# 1x24_relayBoard_011.net
KiCad netlist of a schematic drawn in EAGLE
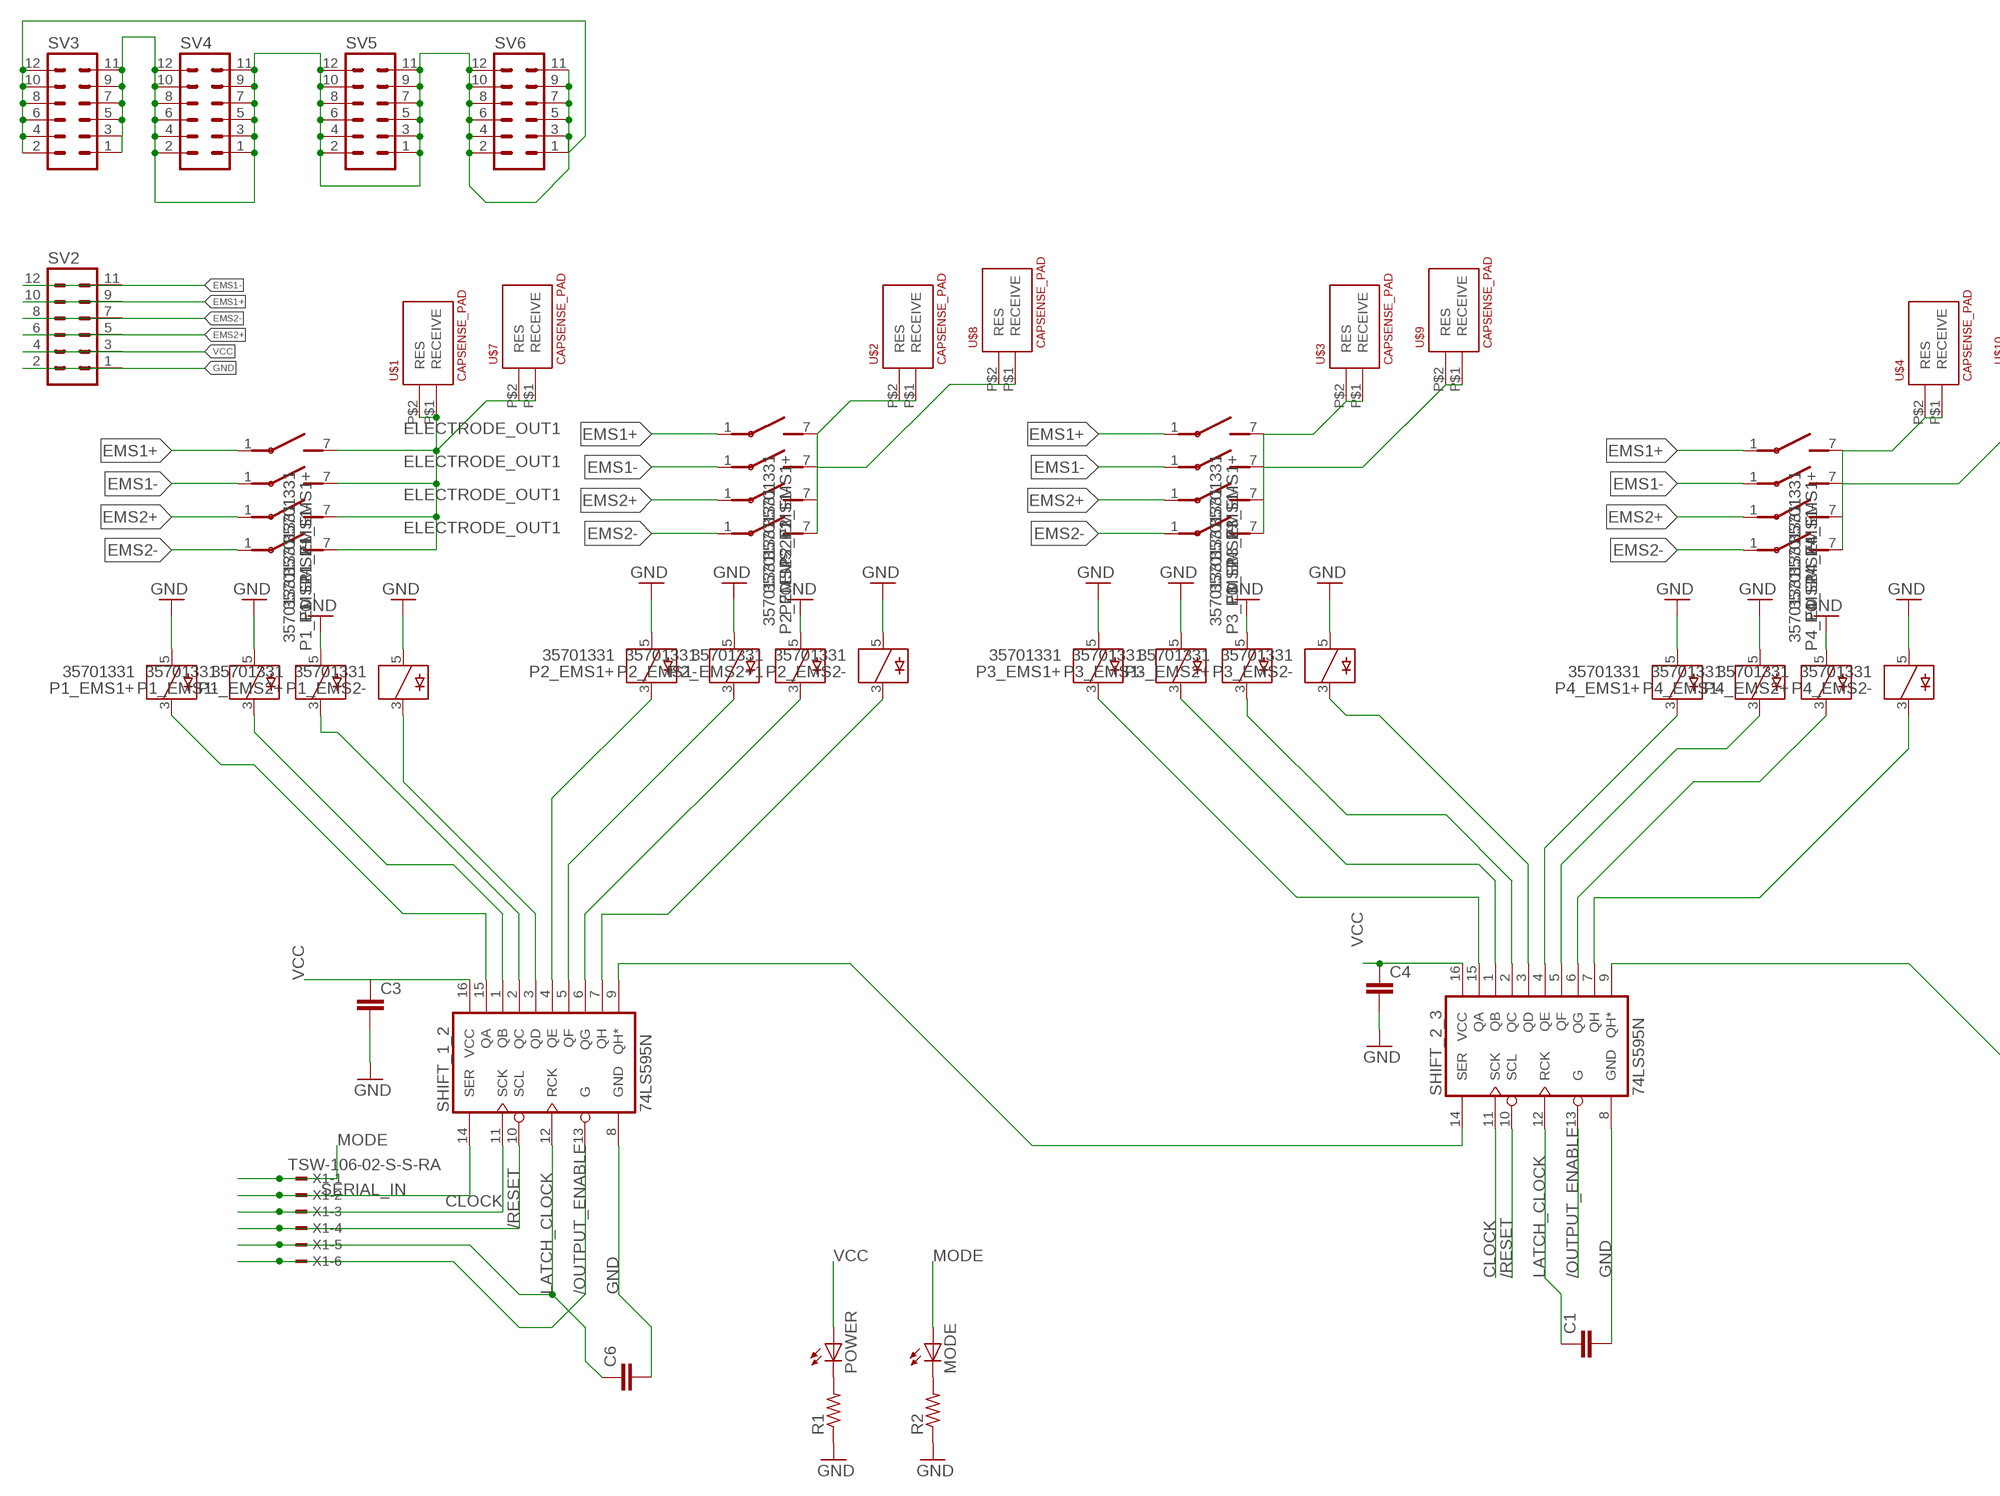
[diagram p0: schematic, sheet 1, part 1 of 2]
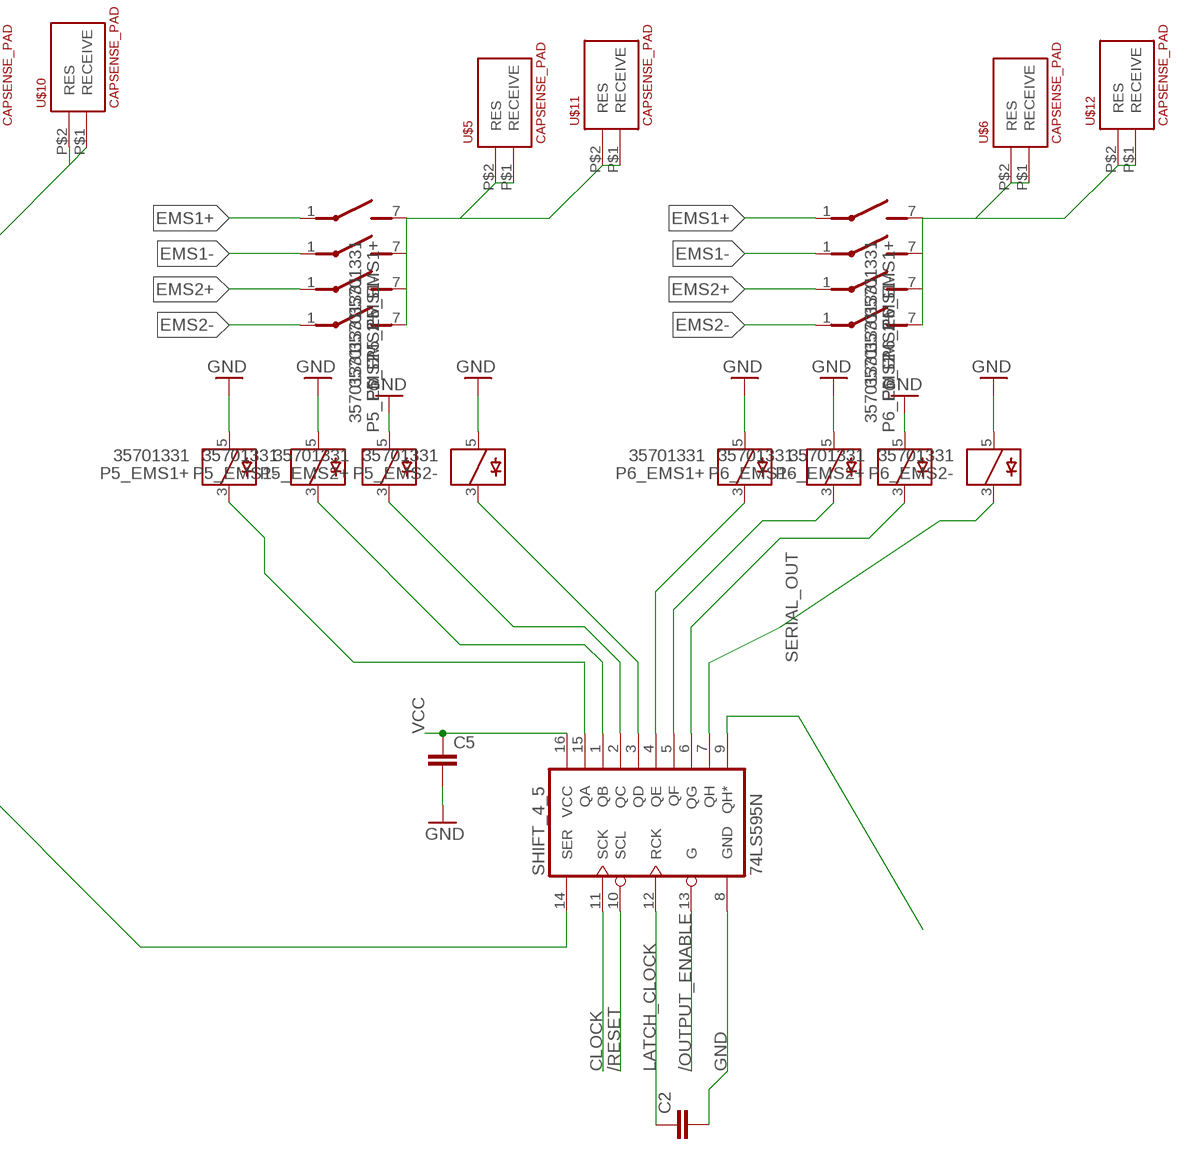
[diagram p1: schematic, sheet 1, part 2 of 2]

(export (version "E")
  (design (tool "Eeschema 10.0.6"))
  (components
    (comp (ref "C1")
      (value "C5/5")
      (footprint "eagle-import:C5B5")
      (libsource (lib "eagle-import") (part "C5/5"))
    )
    (comp (ref "C2")
      (value "C5/5")
      (footprint "eagle-import:C5B5")
      (libsource (lib "eagle-import") (part "C5/5"))
    )
    (comp (ref "C3")
      (value "C5/5")
      (footprint "eagle-import:C5B5")
      (libsource (lib "eagle-import") (part "C5/5"))
    )
    (comp (ref "C4")
      (value "C5/5")
      (footprint "eagle-import:C5B5")
      (libsource (lib "eagle-import") (part "C5/5"))
    )
    (comp (ref "C5")
      (value "C5/5")
      (footprint "eagle-import:C5B5")
      (libsource (lib "eagle-import") (part "C5/5"))
    )
    (comp (ref "C6")
      (value "C5/5")
      (footprint "eagle-import:C5B5")
      (libsource (lib "eagle-import") (part "C5/5"))
    )
    (comp (ref "MODE")
      (value "LED_E")
      (footprint "eagle-import:LED_1206")
      (libsource (lib "eagle-import") (part "LED_E"))
    )
    (comp (ref "P1_EMS1+")
      (value "35701331")
      (footprint "eagle-import:REED")
      (libsource (lib "eagle-import") (part "35701331"))
    )
    (comp (ref "P1_EMS1-")
      (value "35701331")
      (footprint "eagle-import:REED")
      (libsource (lib "eagle-import") (part "35701331"))
    )
    (comp (ref "P1_EMS2+")
      (value "35701331")
      (footprint "eagle-import:REED")
      (libsource (lib "eagle-import") (part "35701331"))
    )
    (comp (ref "P1_EMS2-")
      (value "35701331")
      (footprint "eagle-import:REED")
      (libsource (lib "eagle-import") (part "35701331"))
    )
    (comp (ref "P2_EMS1+")
      (value "35701331")
      (footprint "eagle-import:REED")
      (libsource (lib "eagle-import") (part "35701331"))
    )
    (comp (ref "P2_EMS1-")
      (value "35701331")
      (footprint "eagle-import:REED")
      (libsource (lib "eagle-import") (part "35701331"))
    )
    (comp (ref "P2_EMS2+1")
      (value "35701331")
      (footprint "eagle-import:REED")
      (libsource (lib "eagle-import") (part "35701331"))
    )
    (comp (ref "P2_EMS2-")
      (value "35701331")
      (footprint "eagle-import:REED")
      (libsource (lib "eagle-import") (part "35701331"))
    )
    (comp (ref "P3_EMS1+")
      (value "35701331")
      (footprint "eagle-import:REED")
      (libsource (lib "eagle-import") (part "35701331"))
    )
    (comp (ref "P3_EMS1-")
      (value "35701331")
      (footprint "eagle-import:REED")
      (libsource (lib "eagle-import") (part "35701331"))
    )
    (comp (ref "P3_EMS2+")
      (value "35701331")
      (footprint "eagle-import:REED")
      (libsource (lib "eagle-import") (part "35701331"))
    )
    (comp (ref "P3_EMS2-")
      (value "35701331")
      (footprint "eagle-import:REED")
      (libsource (lib "eagle-import") (part "35701331"))
    )
    (comp (ref "P4_EMS1+")
      (value "35701331")
      (footprint "eagle-import:REED")
      (libsource (lib "eagle-import") (part "35701331"))
    )
    (comp (ref "P4_EMS1-")
      (value "35701331")
      (footprint "eagle-import:REED")
      (libsource (lib "eagle-import") (part "35701331"))
    )
    (comp (ref "P4_EMS2+")
      (value "35701331")
      (footprint "eagle-import:REED")
      (libsource (lib "eagle-import") (part "35701331"))
    )
    (comp (ref "P4_EMS2-")
      (value "35701331")
      (footprint "eagle-import:REED")
      (libsource (lib "eagle-import") (part "35701331"))
    )
    (comp (ref "P5_EMS1+")
      (value "35701331")
      (footprint "eagle-import:REED")
      (libsource (lib "eagle-import") (part "35701331"))
    )
    (comp (ref "P5_EMS1-")
      (value "35701331")
      (footprint "eagle-import:REED")
      (libsource (lib "eagle-import") (part "35701331"))
    )
    (comp (ref "P5_EMS2+")
      (value "35701331")
      (footprint "eagle-import:REED")
      (libsource (lib "eagle-import") (part "35701331"))
    )
    (comp (ref "P5_EMS2-")
      (value "35701331")
      (footprint "eagle-import:REED")
      (libsource (lib "eagle-import") (part "35701331"))
    )
    (comp (ref "P6_EMS1+")
      (value "35701331")
      (footprint "eagle-import:REED")
      (libsource (lib "eagle-import") (part "35701331"))
    )
    (comp (ref "P6_EMS1-")
      (value "35701331")
      (footprint "eagle-import:REED")
      (libsource (lib "eagle-import") (part "35701331"))
    )
    (comp (ref "P6_EMS2+")
      (value "35701331")
      (footprint "eagle-import:REED")
      (libsource (lib "eagle-import") (part "35701331"))
    )
    (comp (ref "P6_EMS2-")
      (value "35701331")
      (footprint "eagle-import:REED")
      (libsource (lib "eagle-import") (part "35701331"))
    )
    (comp (ref "POWER")
      (value "LED_E")
      (footprint "eagle-import:LED_1206")
      (libsource (lib "eagle-import") (part "LED_E"))
    )
    (comp (ref "R1")
      (value "R-US_M1206")
      (footprint "eagle-import:M1206")
      (libsource (lib "eagle-import") (part "R-US_M1206"))
    )
    (comp (ref "R2")
      (value "R-US_M1206")
      (footprint "eagle-import:M1206")
      (libsource (lib "eagle-import") (part "R-US_M1206"))
    )
    (comp (ref "SHIFT_1_2")
      (value "74LS595N")
      (footprint "eagle-import:DIL16")
      (libsource (lib "eagle-import") (part "74595NLS"))
    )
    (comp (ref "SHIFT_2_3")
      (value "74LS595N")
      (footprint "eagle-import:DIL16")
      (libsource (lib "eagle-import") (part "74595NLS"))
    )
    (comp (ref "SHIFT_4_5")
      (value "74LS595N")
      (footprint "eagle-import:DIL16")
      (libsource (lib "eagle-import") (part "74595NLS"))
    )
    (comp (ref "SV2")
      (value "MA06-2")
      (footprint "eagle-import:MA06-2")
      (libsource (lib "eagle-import") (part "MA06-2"))
    )
    (comp (ref "SV3")
      (value "MA06-2")
      (footprint "eagle-import:MA06-2")
      (libsource (lib "eagle-import") (part "MA06-2"))
    )
    (comp (ref "SV4")
      (value "MA06-2")
      (footprint "eagle-import:MA06-2")
      (libsource (lib "eagle-import") (part "MA06-2"))
    )
    (comp (ref "SV5")
      (value "MA06-2")
      (footprint "eagle-import:MA06-2")
      (libsource (lib "eagle-import") (part "MA06-2"))
    )
    (comp (ref "SV6")
      (value "MA06-2")
      (footprint "eagle-import:MA06-2")
      (libsource (lib "eagle-import") (part "MA06-2"))
    )
    (comp (ref "U$1")
      (value "CAPSENSE_PAD")
      (footprint "eagle-import:CAPSENSE_PAD")
      (libsource (lib "eagle-import") (part "CAPSENSE_PAD"))
    )
    (comp (ref "U$2")
      (value "CAPSENSE_PAD")
      (footprint "eagle-import:CAPSENSE_PAD")
      (libsource (lib "eagle-import") (part "CAPSENSE_PAD"))
    )
    (comp (ref "U$3")
      (value "CAPSENSE_PAD")
      (footprint "eagle-import:CAPSENSE_PAD")
      (libsource (lib "eagle-import") (part "CAPSENSE_PAD"))
    )
    (comp (ref "U$4")
      (value "CAPSENSE_PAD")
      (footprint "eagle-import:CAPSENSE_PAD")
      (libsource (lib "eagle-import") (part "CAPSENSE_PAD"))
    )
    (comp (ref "U$5")
      (value "CAPSENSE_PAD")
      (footprint "eagle-import:CAPSENSE_PAD")
      (libsource (lib "eagle-import") (part "CAPSENSE_PAD"))
    )
    (comp (ref "U$6")
      (value "CAPSENSE_PAD")
      (footprint "eagle-import:CAPSENSE_PAD")
      (libsource (lib "eagle-import") (part "CAPSENSE_PAD"))
    )
    (comp (ref "U$7")
      (value "CAPSENSE_PAD")
      (footprint "eagle-import:CAPSENSE_PAD")
      (libsource (lib "eagle-import") (part "CAPSENSE_PAD"))
    )
    (comp (ref "U$8")
      (value "CAPSENSE_PAD")
      (footprint "eagle-import:CAPSENSE_PAD")
      (libsource (lib "eagle-import") (part "CAPSENSE_PAD"))
    )
    (comp (ref "U$9")
      (value "CAPSENSE_PAD")
      (footprint "eagle-import:CAPSENSE_PAD")
      (libsource (lib "eagle-import") (part "CAPSENSE_PAD"))
    )
    (comp (ref "U$10")
      (value "CAPSENSE_PAD")
      (footprint "eagle-import:CAPSENSE_PAD")
      (libsource (lib "eagle-import") (part "CAPSENSE_PAD"))
    )
    (comp (ref "U$11")
      (value "CAPSENSE_PAD")
      (footprint "eagle-import:CAPSENSE_PAD")
      (libsource (lib "eagle-import") (part "CAPSENSE_PAD"))
    )
    (comp (ref "U$12")
      (value "CAPSENSE_PAD")
      (footprint "eagle-import:CAPSENSE_PAD")
      (libsource (lib "eagle-import") (part "CAPSENSE_PAD"))
    )
    (comp (ref "X1")
      (value "TSW-106-02-S-S-RA")
      (footprint "eagle-import:TSW-106-02-S-S-RA")
      (libsource (lib "eagle-import") (part "TSW-106-02-S-S-RA"))
    )
  )
  (nets
    (net (code "1") (name "/CLOCK") (class "Default")
      (node (ref "SHIFT_1_2") (pin "11") (pinfunction "SCK_11") (pintype "input"))
      (node (ref "SHIFT_2_3") (pin "11") (pinfunction "SCK_11") (pintype "input"))
      (node (ref "SHIFT_4_5") (pin "11") (pinfunction "SCK_11") (pintype "input"))
      (node (ref "X1") (pin "3") (pinfunction "1_3") (pintype "passive"))
    )
    (net (code "2") (name "/ELECTRODE_OUT1") (class "Default")
      (node (ref "P1_EMS1+") (pin "7") (pinfunction "S_7") (pintype "passive"))
      (node (ref "P1_EMS1-") (pin "7") (pinfunction "S_7") (pintype "passive"))
      (node (ref "P1_EMS2+") (pin "7") (pinfunction "S_7") (pintype "passive"))
      (node (ref "P1_EMS2-") (pin "7") (pinfunction "S_7") (pintype "passive"))
      (node (ref "U$1") (pin "P$1") (pinfunction "RECEIVE_P$1") (pintype "bidirectional"))
      (node (ref "U$1") (pin "P$2") (pinfunction "RES_P$2") (pintype "bidirectional"))
      (node (ref "U$7") (pin "P$1") (pinfunction "RECEIVE_P$1") (pintype "bidirectional"))
      (node (ref "U$7") (pin "P$2") (pinfunction "RES_P$2") (pintype "bidirectional"))
    )
    (net (code "3") (name "/LATCH_CLOCK") (class "Default")
      (node (ref "C1") (pin "1") (pinfunction "1_1") (pintype "passive"))
      (node (ref "C2") (pin "1") (pinfunction "1_1") (pintype "passive"))
      (node (ref "C6") (pin "1") (pinfunction "1_1") (pintype "passive"))
      (node (ref "SHIFT_1_2") (pin "12") (pinfunction "RCK_12") (pintype "input"))
      (node (ref "SHIFT_2_3") (pin "12") (pinfunction "RCK_12") (pintype "input"))
      (node (ref "SHIFT_4_5") (pin "12") (pinfunction "RCK_12") (pintype "input"))
      (node (ref "X1") (pin "5") (pinfunction "1_5") (pintype "passive"))
    )
    (net (code "4") (name "/MODE") (class "Default")
      (node (ref "MODE") (pin "A") (pinfunction "A_A") (pintype "passive"))
      (node (ref "X1") (pin "1") (pinfunction "1_1") (pintype "passive"))
    )
    (net (code "5") (name "/SERIAL_IN") (class "Default")
      (node (ref "SHIFT_1_2") (pin "14") (pinfunction "SER_14") (pintype "input"))
      (node (ref "X1") (pin "2") (pinfunction "1_2") (pintype "passive"))
    )
    (net (code "6") (name "/SERIAL_OUT") (class "Default")
      (node (ref "SHIFT_4_5") (pin "9") (pinfunction "QH*_9") (pintype "tri_state"))
    )
    (net (code "7") (name "/{slash}OUTPUT_ENABLE") (class "Default")
      (node (ref "SHIFT_1_2") (pin "13") (pinfunction "G_13") (pintype "input"))
      (node (ref "SHIFT_2_3") (pin "13") (pinfunction "G_13") (pintype "input"))
      (node (ref "SHIFT_4_5") (pin "13") (pinfunction "G_13") (pintype "input"))
      (node (ref "X1") (pin "6") (pinfunction "1_6") (pintype "passive"))
    )
    (net (code "8") (name "/{slash}RESET") (class "Default")
      (node (ref "SHIFT_1_2") (pin "10") (pinfunction "SCL_10") (pintype "input"))
      (node (ref "SHIFT_2_3") (pin "10") (pinfunction "SCL_10") (pintype "input"))
      (node (ref "SHIFT_4_5") (pin "10") (pinfunction "SCL_10") (pintype "input"))
      (node (ref "X1") (pin "4") (pinfunction "1_4") (pintype "passive"))
    )
    (net (code "9") (name "EMS1+") (class "Default")
      (node (ref "P1_EMS1+") (pin "1") (pinfunction "P_1") (pintype "passive"))
      (node (ref "P2_EMS1+") (pin "1") (pinfunction "P_1") (pintype "passive"))
      (node (ref "P3_EMS1+") (pin "1") (pinfunction "P_1") (pintype "passive"))
      (node (ref "P4_EMS1+") (pin "1") (pinfunction "P_1") (pintype "passive"))
      (node (ref "P5_EMS1+") (pin "1") (pinfunction "P_1") (pintype "passive"))
      (node (ref "P6_EMS1+") (pin "1") (pinfunction "P_1") (pintype "passive"))
      (node (ref "SV2") (pin "10") (pinfunction "10_10") (pintype "passive"))
      (node (ref "SV2") (pin "9") (pinfunction "9_9") (pintype "passive"))
    )
    (net (code "10") (name "EMS1-") (class "Default")
      (node (ref "P1_EMS1-") (pin "1") (pinfunction "P_1") (pintype "passive"))
      (node (ref "P2_EMS1-") (pin "1") (pinfunction "P_1") (pintype "passive"))
      (node (ref "P3_EMS1-") (pin "1") (pinfunction "P_1") (pintype "passive"))
      (node (ref "P4_EMS1-") (pin "1") (pinfunction "P_1") (pintype "passive"))
      (node (ref "P5_EMS1-") (pin "1") (pinfunction "P_1") (pintype "passive"))
      (node (ref "P6_EMS1-") (pin "1") (pinfunction "P_1") (pintype "passive"))
      (node (ref "SV2") (pin "11") (pinfunction "11_11") (pintype "passive"))
      (node (ref "SV2") (pin "12") (pinfunction "12_12") (pintype "passive"))
    )
    (net (code "11") (name "EMS2+") (class "Default")
      (node (ref "P1_EMS2+") (pin "1") (pinfunction "P_1") (pintype "passive"))
      (node (ref "P2_EMS2+1") (pin "1") (pinfunction "P_1") (pintype "passive"))
      (node (ref "P3_EMS2+") (pin "1") (pinfunction "P_1") (pintype "passive"))
      (node (ref "P4_EMS2+") (pin "1") (pinfunction "P_1") (pintype "passive"))
      (node (ref "P5_EMS2+") (pin "1") (pinfunction "P_1") (pintype "passive"))
      (node (ref "P6_EMS2+") (pin "1") (pinfunction "P_1") (pintype "passive"))
      (node (ref "SV2") (pin "5") (pinfunction "5_5") (pintype "passive"))
      (node (ref "SV2") (pin "6") (pinfunction "6_6") (pintype "passive"))
    )
    (net (code "12") (name "EMS2-") (class "Default")
      (node (ref "P1_EMS2-") (pin "1") (pinfunction "P_1") (pintype "passive"))
      (node (ref "P2_EMS2-") (pin "1") (pinfunction "P_1") (pintype "passive"))
      (node (ref "P3_EMS2-") (pin "1") (pinfunction "P_1") (pintype "passive"))
      (node (ref "P4_EMS2-") (pin "1") (pinfunction "P_1") (pintype "passive"))
      (node (ref "P5_EMS2-") (pin "1") (pinfunction "P_1") (pintype "passive"))
      (node (ref "P6_EMS2-") (pin "1") (pinfunction "P_1") (pintype "passive"))
      (node (ref "SV2") (pin "7") (pinfunction "7_7") (pintype "passive"))
      (node (ref "SV2") (pin "8") (pinfunction "8_8") (pintype "passive"))
    )
    (net (code "13") (name "GND") (class "Default")
      (node (ref "C1") (pin "2") (pinfunction "2_2") (pintype "passive"))
      (node (ref "C2") (pin "2") (pinfunction "2_2") (pintype "passive"))
      (node (ref "C3") (pin "2") (pinfunction "2_2") (pintype "passive"))
      (node (ref "C4") (pin "2") (pinfunction "2_2") (pintype "passive"))
      (node (ref "C5") (pin "2") (pinfunction "2_2") (pintype "passive"))
      (node (ref "C6") (pin "2") (pinfunction "2_2") (pintype "passive"))
      (node (ref "P1_EMS1+") (pin "5") (pinfunction "5_5") (pintype "passive"))
      (node (ref "P1_EMS1-") (pin "5") (pinfunction "5_5") (pintype "passive"))
      (node (ref "P1_EMS2+") (pin "5") (pinfunction "5_5") (pintype "passive"))
      (node (ref "P1_EMS2-") (pin "5") (pinfunction "5_5") (pintype "passive"))
      (node (ref "P2_EMS1+") (pin "5") (pinfunction "5_5") (pintype "passive"))
      (node (ref "P2_EMS1-") (pin "5") (pinfunction "5_5") (pintype "passive"))
      (node (ref "P2_EMS2+1") (pin "5") (pinfunction "5_5") (pintype "passive"))
      (node (ref "P2_EMS2-") (pin "5") (pinfunction "5_5") (pintype "passive"))
      (node (ref "P3_EMS1+") (pin "5") (pinfunction "5_5") (pintype "passive"))
      (node (ref "P3_EMS1-") (pin "5") (pinfunction "5_5") (pintype "passive"))
      (node (ref "P3_EMS2+") (pin "5") (pinfunction "5_5") (pintype "passive"))
      (node (ref "P3_EMS2-") (pin "5") (pinfunction "5_5") (pintype "passive"))
      (node (ref "P4_EMS1+") (pin "5") (pinfunction "5_5") (pintype "passive"))
      (node (ref "P4_EMS1-") (pin "5") (pinfunction "5_5") (pintype "passive"))
      (node (ref "P4_EMS2+") (pin "5") (pinfunction "5_5") (pintype "passive"))
      (node (ref "P4_EMS2-") (pin "5") (pinfunction "5_5") (pintype "passive"))
      (node (ref "P5_EMS1+") (pin "5") (pinfunction "5_5") (pintype "passive"))
      (node (ref "P5_EMS1-") (pin "5") (pinfunction "5_5") (pintype "passive"))
      (node (ref "P5_EMS2+") (pin "5") (pinfunction "5_5") (pintype "passive"))
      (node (ref "P5_EMS2-") (pin "5") (pinfunction "5_5") (pintype "passive"))
      (node (ref "P6_EMS1+") (pin "5") (pinfunction "5_5") (pintype "passive"))
      (node (ref "P6_EMS1-") (pin "5") (pinfunction "5_5") (pintype "passive"))
      (node (ref "P6_EMS2+") (pin "5") (pinfunction "5_5") (pintype "passive"))
      (node (ref "P6_EMS2-") (pin "5") (pinfunction "5_5") (pintype "passive"))
      (node (ref "R1") (pin "1") (pinfunction "1_1") (pintype "passive"))
      (node (ref "R2") (pin "1") (pinfunction "1_1") (pintype "passive"))
      (node (ref "SHIFT_1_2") (pin "8") (pinfunction "GND_8") (pintype "power_in"))
      (node (ref "SHIFT_2_3") (pin "8") (pinfunction "GND_8") (pintype "power_in"))
      (node (ref "SHIFT_4_5") (pin "8") (pinfunction "GND_8") (pintype "power_in"))
      (node (ref "SV2") (pin "1") (pinfunction "1_1") (pintype "passive"))
      (node (ref "SV2") (pin "2") (pinfunction "2_2") (pintype "passive"))
      (node (ref "SV3") (pin "1") (pinfunction "1_1") (pintype "passive"))
      (node (ref "SV3") (pin "10") (pinfunction "10_10") (pintype "passive"))
      (node (ref "SV3") (pin "11") (pinfunction "11_11") (pintype "passive"))
      (node (ref "SV3") (pin "12") (pinfunction "12_12") (pintype "passive"))
      (node (ref "SV3") (pin "2") (pinfunction "2_2") (pintype "passive"))
      (node (ref "SV3") (pin "3") (pinfunction "3_3") (pintype "passive"))
      (node (ref "SV3") (pin "4") (pinfunction "4_4") (pintype "passive"))
      (node (ref "SV3") (pin "5") (pinfunction "5_5") (pintype "passive"))
      (node (ref "SV3") (pin "6") (pinfunction "6_6") (pintype "passive"))
      (node (ref "SV3") (pin "7") (pinfunction "7_7") (pintype "passive"))
      (node (ref "SV3") (pin "8") (pinfunction "8_8") (pintype "passive"))
      (node (ref "SV3") (pin "9") (pinfunction "9_9") (pintype "passive"))
      (node (ref "SV4") (pin "1") (pinfunction "1_1") (pintype "passive"))
      (node (ref "SV4") (pin "10") (pinfunction "10_10") (pintype "passive"))
      (node (ref "SV4") (pin "11") (pinfunction "11_11") (pintype "passive"))
      (node (ref "SV4") (pin "12") (pinfunction "12_12") (pintype "passive"))
      (node (ref "SV4") (pin "2") (pinfunction "2_2") (pintype "passive"))
      (node (ref "SV4") (pin "3") (pinfunction "3_3") (pintype "passive"))
      (node (ref "SV4") (pin "4") (pinfunction "4_4") (pintype "passive"))
      (node (ref "SV4") (pin "5") (pinfunction "5_5") (pintype "passive"))
      (node (ref "SV4") (pin "6") (pinfunction "6_6") (pintype "passive"))
      (node (ref "SV4") (pin "7") (pinfunction "7_7") (pintype "passive"))
      (node (ref "SV4") (pin "8") (pinfunction "8_8") (pintype "passive"))
      (node (ref "SV4") (pin "9") (pinfunction "9_9") (pintype "passive"))
      (node (ref "SV5") (pin "1") (pinfunction "1_1") (pintype "passive"))
      (node (ref "SV5") (pin "10") (pinfunction "10_10") (pintype "passive"))
      (node (ref "SV5") (pin "11") (pinfunction "11_11") (pintype "passive"))
      (node (ref "SV5") (pin "12") (pinfunction "12_12") (pintype "passive"))
      (node (ref "SV5") (pin "2") (pinfunction "2_2") (pintype "passive"))
      (node (ref "SV5") (pin "3") (pinfunction "3_3") (pintype "passive"))
      (node (ref "SV5") (pin "4") (pinfunction "4_4") (pintype "passive"))
      (node (ref "SV5") (pin "5") (pinfunction "5_5") (pintype "passive"))
      (node (ref "SV5") (pin "6") (pinfunction "6_6") (pintype "passive"))
      (node (ref "SV5") (pin "7") (pinfunction "7_7") (pintype "passive"))
      (node (ref "SV5") (pin "8") (pinfunction "8_8") (pintype "passive"))
      (node (ref "SV5") (pin "9") (pinfunction "9_9") (pintype "passive"))
      (node (ref "SV6") (pin "1") (pinfunction "1_1") (pintype "passive"))
      (node (ref "SV6") (pin "10") (pinfunction "10_10") (pintype "passive"))
      (node (ref "SV6") (pin "11") (pinfunction "11_11") (pintype "passive"))
      (node (ref "SV6") (pin "12") (pinfunction "12_12") (pintype "passive"))
      (node (ref "SV6") (pin "2") (pinfunction "2_2") (pintype "passive"))
      (node (ref "SV6") (pin "3") (pinfunction "3_3") (pintype "passive"))
      (node (ref "SV6") (pin "4") (pinfunction "4_4") (pintype "passive"))
      (node (ref "SV6") (pin "5") (pinfunction "5_5") (pintype "passive"))
      (node (ref "SV6") (pin "6") (pinfunction "6_6") (pintype "passive"))
      (node (ref "SV6") (pin "7") (pinfunction "7_7") (pintype "passive"))
      (node (ref "SV6") (pin "8") (pinfunction "8_8") (pintype "passive"))
      (node (ref "SV6") (pin "9") (pinfunction "9_9") (pintype "passive"))
    )
    (net (code "14") (name "Net-(MODE-PadC)") (class "Default")
      (node (ref "MODE") (pin "C") (pinfunction "C_C") (pintype "passive"))
      (node (ref "R2") (pin "2") (pinfunction "2_2") (pintype "passive"))
    )
    (net (code "15") (name "Net-(P2_EMS1+B-S)") (class "Default")
      (node (ref "P2_EMS1+") (pin "7") (pinfunction "S_7") (pintype "passive"))
      (node (ref "P2_EMS1-") (pin "7") (pinfunction "S_7") (pintype "passive"))
      (node (ref "P2_EMS2+1") (pin "7") (pinfunction "S_7") (pintype "passive"))
      (node (ref "P2_EMS2-") (pin "7") (pinfunction "S_7") (pintype "passive"))
      (node (ref "U$2") (pin "P$1") (pinfunction "RECEIVE_P$1") (pintype "bidirectional"))
      (node (ref "U$2") (pin "P$2") (pinfunction "RES_P$2") (pintype "bidirectional"))
      (node (ref "U$8") (pin "P$1") (pinfunction "RECEIVE_P$1") (pintype "bidirectional"))
      (node (ref "U$8") (pin "P$2") (pinfunction "RES_P$2") (pintype "bidirectional"))
    )
    (net (code "16") (name "Net-(P3_EMS1+B-S)") (class "Default")
      (node (ref "P3_EMS1+") (pin "7") (pinfunction "S_7") (pintype "passive"))
      (node (ref "P3_EMS1-") (pin "7") (pinfunction "S_7") (pintype "passive"))
      (node (ref "P3_EMS2+") (pin "7") (pinfunction "S_7") (pintype "passive"))
      (node (ref "P3_EMS2-") (pin "7") (pinfunction "S_7") (pintype "passive"))
      (node (ref "U$3") (pin "P$1") (pinfunction "RECEIVE_P$1") (pintype "bidirectional"))
      (node (ref "U$3") (pin "P$2") (pinfunction "RES_P$2") (pintype "bidirectional"))
      (node (ref "U$9") (pin "P$1") (pinfunction "RECEIVE_P$1") (pintype "bidirectional"))
      (node (ref "U$9") (pin "P$2") (pinfunction "RES_P$2") (pintype "bidirectional"))
    )
    (net (code "17") (name "Net-(P4_EMS1+B-S)") (class "Default")
      (node (ref "P4_EMS1+") (pin "7") (pinfunction "S_7") (pintype "passive"))
      (node (ref "P4_EMS1-") (pin "7") (pinfunction "S_7") (pintype "passive"))
      (node (ref "P4_EMS2+") (pin "7") (pinfunction "S_7") (pintype "passive"))
      (node (ref "P4_EMS2-") (pin "7") (pinfunction "S_7") (pintype "passive"))
      (node (ref "U$10") (pin "P$1") (pinfunction "RECEIVE_P$1") (pintype "bidirectional"))
      (node (ref "U$10") (pin "P$2") (pinfunction "RES_P$2") (pintype "bidirectional"))
      (node (ref "U$4") (pin "P$1") (pinfunction "RECEIVE_P$1") (pintype "bidirectional"))
      (node (ref "U$4") (pin "P$2") (pinfunction "RES_P$2") (pintype "bidirectional"))
    )
    (net (code "18") (name "Net-(P5_EMS1+B-S)") (class "Default")
      (node (ref "P5_EMS1+") (pin "7") (pinfunction "S_7") (pintype "passive"))
      (node (ref "P5_EMS1-") (pin "7") (pinfunction "S_7") (pintype "passive"))
      (node (ref "P5_EMS2+") (pin "7") (pinfunction "S_7") (pintype "passive"))
      (node (ref "P5_EMS2-") (pin "7") (pinfunction "S_7") (pintype "passive"))
      (node (ref "U$11") (pin "P$1") (pinfunction "RECEIVE_P$1") (pintype "bidirectional"))
      (node (ref "U$11") (pin "P$2") (pinfunction "RES_P$2") (pintype "bidirectional"))
      (node (ref "U$5") (pin "P$1") (pinfunction "RECEIVE_P$1") (pintype "bidirectional"))
      (node (ref "U$5") (pin "P$2") (pinfunction "RES_P$2") (pintype "bidirectional"))
    )
    (net (code "19") (name "Net-(P6_EMS1+B-S)") (class "Default")
      (node (ref "P6_EMS1+") (pin "7") (pinfunction "S_7") (pintype "passive"))
      (node (ref "P6_EMS1-") (pin "7") (pinfunction "S_7") (pintype "passive"))
      (node (ref "P6_EMS2+") (pin "7") (pinfunction "S_7") (pintype "passive"))
      (node (ref "P6_EMS2-") (pin "7") (pinfunction "S_7") (pintype "passive"))
      (node (ref "U$12") (pin "P$1") (pinfunction "RECEIVE_P$1") (pintype "bidirectional"))
      (node (ref "U$12") (pin "P$2") (pinfunction "RES_P$2") (pintype "bidirectional"))
      (node (ref "U$6") (pin "P$1") (pinfunction "RECEIVE_P$1") (pintype "bidirectional"))
      (node (ref "U$6") (pin "P$2") (pinfunction "RES_P$2") (pintype "bidirectional"))
    )
    (net (code "20") (name "Net-(POWER-PadC)") (class "Default")
      (node (ref "POWER") (pin "C") (pinfunction "C_C") (pintype "passive"))
      (node (ref "R1") (pin "2") (pinfunction "2_2") (pintype "passive"))
    )
    (net (code "21") (name "Net-(SHIFT_1_2-QA)") (class "Default")
      (node (ref "P1_EMS1+") (pin "3") (pinfunction "3_3") (pintype "passive"))
      (node (ref "SHIFT_1_2") (pin "15") (pinfunction "QA_15") (pintype "tri_state"))
    )
    (net (code "22") (name "Net-(SHIFT_1_2-QB)") (class "Default")
      (node (ref "P1_EMS1-") (pin "3") (pinfunction "3_3") (pintype "passive"))
      (node (ref "SHIFT_1_2") (pin "1") (pinfunction "QB_1") (pintype "tri_state"))
    )
    (net (code "23") (name "Net-(SHIFT_1_2-QC)") (class "Default")
      (node (ref "P1_EMS2+") (pin "3") (pinfunction "3_3") (pintype "passive"))
      (node (ref "SHIFT_1_2") (pin "2") (pinfunction "QC_2") (pintype "tri_state"))
    )
    (net (code "24") (name "Net-(SHIFT_1_2-QD)") (class "Default")
      (node (ref "P1_EMS2-") (pin "3") (pinfunction "3_3") (pintype "passive"))
      (node (ref "SHIFT_1_2") (pin "3") (pinfunction "QD_3") (pintype "tri_state"))
    )
    (net (code "25") (name "Net-(SHIFT_1_2-QE)") (class "Default")
      (node (ref "P2_EMS1+") (pin "3") (pinfunction "3_3") (pintype "passive"))
      (node (ref "SHIFT_1_2") (pin "4") (pinfunction "QE_4") (pintype "tri_state"))
    )
    (net (code "26") (name "Net-(SHIFT_1_2-QF)") (class "Default")
      (node (ref "P2_EMS1-") (pin "3") (pinfunction "3_3") (pintype "passive"))
      (node (ref "SHIFT_1_2") (pin "5") (pinfunction "QF_5") (pintype "tri_state"))
    )
    (net (code "27") (name "Net-(SHIFT_1_2-QG)") (class "Default")
      (node (ref "P2_EMS2+1") (pin "3") (pinfunction "3_3") (pintype "passive"))
      (node (ref "SHIFT_1_2") (pin "6") (pinfunction "QG_6") (pintype "tri_state"))
    )
    (net (code "28") (name "Net-(SHIFT_1_2-QH)") (class "Default")
      (node (ref "P2_EMS2-") (pin "3") (pinfunction "3_3") (pintype "passive"))
      (node (ref "SHIFT_1_2") (pin "7") (pinfunction "QH_7") (pintype "tri_state"))
    )
    (net (code "29") (name "Net-(SHIFT_1_2-QH*)") (class "Default")
      (node (ref "SHIFT_1_2") (pin "9") (pinfunction "QH*_9") (pintype "tri_state"))
      (node (ref "SHIFT_2_3") (pin "14") (pinfunction "SER_14") (pintype "input"))
    )
    (net (code "30") (name "Net-(SHIFT_2_3-QA)") (class "Default")
      (node (ref "P3_EMS1+") (pin "3") (pinfunction "3_3") (pintype "passive"))
      (node (ref "SHIFT_2_3") (pin "15") (pinfunction "QA_15") (pintype "tri_state"))
    )
    (net (code "31") (name "Net-(SHIFT_2_3-QB)") (class "Default")
      (node (ref "P3_EMS1-") (pin "3") (pinfunction "3_3") (pintype "passive"))
      (node (ref "SHIFT_2_3") (pin "1") (pinfunction "QB_1") (pintype "tri_state"))
    )
    (net (code "32") (name "Net-(SHIFT_2_3-QC)") (class "Default")
      (node (ref "P3_EMS2+") (pin "3") (pinfunction "3_3") (pintype "passive"))
      (node (ref "SHIFT_2_3") (pin "2") (pinfunction "QC_2") (pintype "tri_state"))
    )
    (net (code "33") (name "Net-(SHIFT_2_3-QD)") (class "Default")
      (node (ref "P3_EMS2-") (pin "3") (pinfunction "3_3") (pintype "passive"))
      (node (ref "SHIFT_2_3") (pin "3") (pinfunction "QD_3") (pintype "tri_state"))
    )
    (net (code "34") (name "Net-(SHIFT_2_3-QE)") (class "Default")
      (node (ref "P4_EMS1+") (pin "3") (pinfunction "3_3") (pintype "passive"))
      (node (ref "SHIFT_2_3") (pin "4") (pinfunction "QE_4") (pintype "tri_state"))
    )
    (net (code "35") (name "Net-(SHIFT_2_3-QF)") (class "Default")
      (node (ref "P4_EMS1-") (pin "3") (pinfunction "3_3") (pintype "passive"))
      (node (ref "SHIFT_2_3") (pin "5") (pinfunction "QF_5") (pintype "tri_state"))
    )
    (net (code "36") (name "Net-(SHIFT_2_3-QG)") (class "Default")
      (node (ref "P4_EMS2+") (pin "3") (pinfunction "3_3") (pintype "passive"))
      (node (ref "SHIFT_2_3") (pin "6") (pinfunction "QG_6") (pintype "tri_state"))
    )
    (net (code "37") (name "Net-(SHIFT_2_3-QH)") (class "Default")
      (node (ref "P4_EMS2-") (pin "3") (pinfunction "3_3") (pintype "passive"))
      (node (ref "SHIFT_2_3") (pin "7") (pinfunction "QH_7") (pintype "tri_state"))
    )
    (net (code "38") (name "Net-(SHIFT_2_3-QH*)") (class "Default")
      (node (ref "SHIFT_2_3") (pin "9") (pinfunction "QH*_9") (pintype "tri_state"))
      (node (ref "SHIFT_4_5") (pin "14") (pinfunction "SER_14") (pintype "input"))
    )
    (net (code "39") (name "Net-(SHIFT_4_5-QA)") (class "Default")
      (node (ref "P5_EMS1+") (pin "3") (pinfunction "3_3") (pintype "passive"))
      (node (ref "SHIFT_4_5") (pin "15") (pinfunction "QA_15") (pintype "tri_state"))
    )
    (net (code "40") (name "Net-(SHIFT_4_5-QB)") (class "Default")
      (node (ref "P5_EMS1-") (pin "3") (pinfunction "3_3") (pintype "passive"))
      (node (ref "SHIFT_4_5") (pin "1") (pinfunction "QB_1") (pintype "tri_state"))
    )
    (net (code "41") (name "Net-(SHIFT_4_5-QC)") (class "Default")
      (node (ref "P5_EMS2+") (pin "3") (pinfunction "3_3") (pintype "passive"))
      (node (ref "SHIFT_4_5") (pin "2") (pinfunction "QC_2") (pintype "tri_state"))
    )
    (net (code "42") (name "Net-(SHIFT_4_5-QD)") (class "Default")
      (node (ref "P5_EMS2-") (pin "3") (pinfunction "3_3") (pintype "passive"))
      (node (ref "SHIFT_4_5") (pin "3") (pinfunction "QD_3") (pintype "tri_state"))
    )
    (net (code "43") (name "Net-(SHIFT_4_5-QE)") (class "Default")
      (node (ref "P6_EMS1+") (pin "3") (pinfunction "3_3") (pintype "passive"))
      (node (ref "SHIFT_4_5") (pin "4") (pinfunction "QE_4") (pintype "tri_state"))
    )
    (net (code "44") (name "Net-(SHIFT_4_5-QF)") (class "Default")
      (node (ref "P6_EMS1-") (pin "3") (pinfunction "3_3") (pintype "passive"))
      (node (ref "SHIFT_4_5") (pin "5") (pinfunction "QF_5") (pintype "tri_state"))
    )
    (net (code "45") (name "Net-(SHIFT_4_5-QG)") (class "Default")
      (node (ref "P6_EMS2+") (pin "3") (pinfunction "3_3") (pintype "passive"))
      (node (ref "SHIFT_4_5") (pin "6") (pinfunction "QG_6") (pintype "tri_state"))
    )
    (net (code "46") (name "Net-(SHIFT_4_5-QH)") (class "Default")
      (node (ref "P6_EMS2-") (pin "3") (pinfunction "3_3") (pintype "passive"))
      (node (ref "SHIFT_4_5") (pin "7") (pinfunction "QH_7") (pintype "tri_state"))
    )
    (net (code "47") (name "VCC") (class "Default")
      (node (ref "C3") (pin "1") (pinfunction "1_1") (pintype "passive"))
      (node (ref "C4") (pin "1") (pinfunction "1_1") (pintype "passive"))
      (node (ref "C5") (pin "1") (pinfunction "1_1") (pintype "passive"))
      (node (ref "POWER") (pin "A") (pinfunction "A_A") (pintype "passive"))
      (node (ref "SHIFT_1_2") (pin "16") (pinfunction "VCC_16") (pintype "power_in"))
      (node (ref "SHIFT_2_3") (pin "16") (pinfunction "VCC_16") (pintype "power_in"))
      (node (ref "SHIFT_4_5") (pin "16") (pinfunction "VCC_16") (pintype "power_in"))
      (node (ref "SV2") (pin "3") (pinfunction "3_3") (pintype "passive"))
      (node (ref "SV2") (pin "4") (pinfunction "4_4") (pintype "passive"))
    )
  )
)
